# smartGarden_Driver_Rev01.net
KiCad netlist of a schematic drawn in Altium Designer
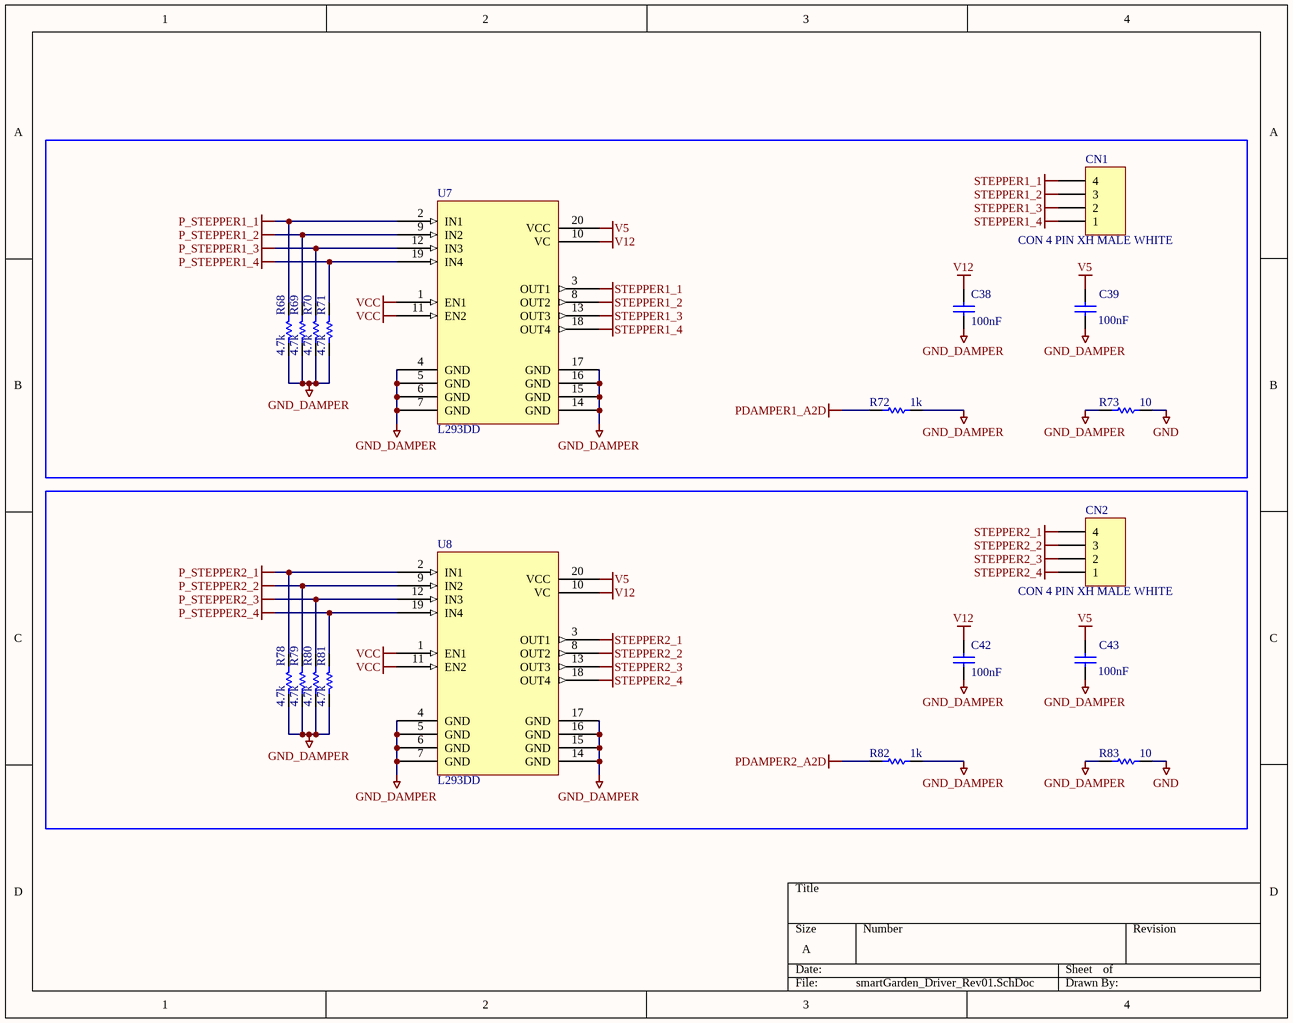
[diagram p0: smartGarden_Driver_Rev01.SchDoc]

(export (version "E")
  (design (tool "Eeschema 10.0.6"))
  (components
    (comp (ref "C38")
      (value "100nF")
      (footprint "0805_SMD")
      (description "Capacitor (Semiconductor SIM Model)")
      (fields (field (name "PUBLISHER") "Altium Limited"))
      (libsource (lib "Miscellaneous Devices") (part "Cap Semi"))
    )
    (comp (ref "C39")
      (value "100nF")
      (footprint "0805_SMD")
      (description "Capacitor (Semiconductor SIM Model)")
      (fields (field (name "PUBLISHER") "Altium Limited"))
      (libsource (lib "Miscellaneous Devices") (part "Cap Semi"))
    )
    (comp (ref "C42")
      (value "100nF")
      (footprint "0805_SMD")
      (description "Capacitor (Semiconductor SIM Model)")
      (fields (field (name "PUBLISHER") "Altium Limited"))
      (libsource (lib "Miscellaneous Devices") (part "Cap Semi"))
    )
    (comp (ref "C43")
      (value "100nF")
      (footprint "0805_SMD")
      (description "Capacitor (Semiconductor SIM Model)")
      (fields (field (name "PUBLISHER") "Altium Limited"))
      (libsource (lib "Miscellaneous Devices") (part "Cap Semi"))
    )
    (comp (ref "CN1")
      (value "CON 4 PIN XH MALE WHITE")
      (footprint "CON4_XH")
      (description "Header, 4-Pin")
      (fields (field (name "PUBLISHER") "Altium Limited"))
      (libsource (lib "Miscellaneous Connectors") (part "Header 4"))
    )
    (comp (ref "CN2")
      (value "CON 4 PIN XH MALE WHITE")
      (footprint "CON4_XH")
      (description "Header, 4-Pin")
      (fields (field (name "PUBLISHER") "Altium Limited"))
      (libsource (lib "Miscellaneous Connectors") (part "Header 4"))
    )
    (comp (ref "R68")
      (value "4.7k")
      (footprint "1206_smd")
      (description "Resistor")
      (fields (field (name "PUBLISHER") "Altium Limited"))
      (libsource (lib "Miscellaneous Devices") (part "Res1"))
    )
    (comp (ref "R69")
      (value "4.7k")
      (footprint "0805_smd")
      (description "Resistor")
      (fields (field (name "PUBLISHER") "Altium Limited"))
      (libsource (lib "Miscellaneous Devices") (part "Res1"))
    )
    (comp (ref "R70")
      (value "4.7k")
      (footprint "0805_smd")
      (description "Resistor")
      (fields (field (name "PUBLISHER") "Altium Limited"))
      (libsource (lib "Miscellaneous Devices") (part "Res1"))
    )
    (comp (ref "R71")
      (value "4.7k")
      (footprint "1206_smd")
      (description "Resistor")
      (fields (field (name "PUBLISHER") "Altium Limited"))
      (libsource (lib "Miscellaneous Devices") (part "Res1"))
    )
    (comp (ref "R72")
      (value "1k")
      (footprint "1206_smd")
      (description "Resistor")
      (fields (field (name "PUBLISHER") "Altium Limited"))
      (libsource (lib "Miscellaneous Devices") (part "Res1"))
    )
    (comp (ref "R73")
      (value "10")
      (footprint "1206_smd")
      (description "Resistor")
      (fields (field (name "PUBLISHER") "Altium Limited"))
      (libsource (lib "Miscellaneous Devices") (part "Res1"))
    )
    (comp (ref "R78")
      (value "4.7k")
      (footprint "1206_smd")
      (description "Resistor")
      (fields (field (name "PUBLISHER") "Altium Limited"))
      (libsource (lib "Miscellaneous Devices") (part "Res1"))
    )
    (comp (ref "R79")
      (value "4.7k")
      (footprint "0805_smd")
      (description "Resistor")
      (fields (field (name "PUBLISHER") "Altium Limited"))
      (libsource (lib "Miscellaneous Devices") (part "Res1"))
    )
    (comp (ref "R80")
      (value "4.7k")
      (footprint "0805_smd")
      (description "Resistor")
      (fields (field (name "PUBLISHER") "Altium Limited"))
      (libsource (lib "Miscellaneous Devices") (part "Res1"))
    )
    (comp (ref "R81")
      (value "4.7k")
      (footprint "1206_smd")
      (description "Resistor")
      (fields (field (name "PUBLISHER") "Altium Limited"))
      (libsource (lib "Miscellaneous Devices") (part "Res1"))
    )
    (comp (ref "R82")
      (value "1k")
      (footprint "1206_smd")
      (description "Resistor")
      (fields (field (name "PUBLISHER") "Altium Limited"))
      (libsource (lib "Miscellaneous Devices") (part "Res1"))
    )
    (comp (ref "R83")
      (value "10")
      (footprint "1206_smd")
      (description "Resistor")
      (fields (field (name "PUBLISHER") "Altium Limited"))
      (libsource (lib "Miscellaneous Devices") (part "Res1"))
    )
    (comp (ref "U7") (value "L293DD") (footprint "SOP20") (libsource (lib "SchLib426") (part "L293DD")))
    (comp (ref "U8") (value "L293DD") (footprint "SOP20") (libsource (lib "SchLib426") (part "L293DD")))
  )
  (nets
    (net (code "1") (name "GND") (class "Default")
      (node (ref "R73") (pin "1") (pinfunction "1_1") (pintype "passive"))
      (node (ref "R83") (pin "1") (pinfunction "1_1") (pintype "passive"))
    )
    (net (code "2") (name "GND_DAMPER") (class "Default")
      (node (ref "C38") (pin "1") (pinfunction "1_1") (pintype "passive"))
      (node (ref "C39") (pin "1") (pinfunction "1_1") (pintype "passive"))
      (node (ref "C42") (pin "1") (pinfunction "1_1") (pintype "passive"))
      (node (ref "C43") (pin "1") (pinfunction "1_1") (pintype "passive"))
      (node (ref "R68") (pin "1") (pinfunction "1_1") (pintype "passive"))
      (node (ref "R69") (pin "1") (pinfunction "1_1") (pintype "passive"))
      (node (ref "R70") (pin "1") (pinfunction "1_1") (pintype "passive"))
      (node (ref "R71") (pin "1") (pinfunction "1_1") (pintype "passive"))
      (node (ref "R72") (pin "1") (pinfunction "1_1") (pintype "passive"))
      (node (ref "R73") (pin "2") (pinfunction "2_2") (pintype "passive"))
      (node (ref "R78") (pin "1") (pinfunction "1_1") (pintype "passive"))
      (node (ref "R79") (pin "1") (pinfunction "1_1") (pintype "passive"))
      (node (ref "R80") (pin "1") (pinfunction "1_1") (pintype "passive"))
      (node (ref "R81") (pin "1") (pinfunction "1_1") (pintype "passive"))
      (node (ref "R82") (pin "1") (pinfunction "1_1") (pintype "passive"))
      (node (ref "R83") (pin "2") (pinfunction "2_2") (pintype "passive"))
      (node (ref "U7") (pin "14") (pinfunction "GND_14") (pintype "power_in"))
      (node (ref "U7") (pin "15") (pinfunction "GND_15") (pintype "power_in"))
      (node (ref "U7") (pin "16") (pinfunction "GND_16") (pintype "power_in"))
      (node (ref "U7") (pin "17") (pinfunction "GND_17") (pintype "power_in"))
      (node (ref "U7") (pin "4") (pinfunction "GND_4") (pintype "power_in"))
      (node (ref "U7") (pin "5") (pinfunction "GND_5") (pintype "power_in"))
      (node (ref "U7") (pin "6") (pinfunction "GND_6") (pintype "power_in"))
      (node (ref "U7") (pin "7") (pinfunction "GND_7") (pintype "power_in"))
      (node (ref "U8") (pin "14") (pinfunction "GND_14") (pintype "power_in"))
      (node (ref "U8") (pin "15") (pinfunction "GND_15") (pintype "power_in"))
      (node (ref "U8") (pin "16") (pinfunction "GND_16") (pintype "power_in"))
      (node (ref "U8") (pin "17") (pinfunction "GND_17") (pintype "power_in"))
      (node (ref "U8") (pin "4") (pinfunction "GND_4") (pintype "power_in"))
      (node (ref "U8") (pin "5") (pinfunction "GND_5") (pintype "power_in"))
      (node (ref "U8") (pin "6") (pinfunction "GND_6") (pintype "power_in"))
      (node (ref "U8") (pin "7") (pinfunction "GND_7") (pintype "power_in"))
    )
    (net (code "3") (name "PDAMPER1_A2D") (class "Default")
      (node (ref "R72") (pin "2") (pinfunction "2_2") (pintype "passive"))
    )
    (net (code "4") (name "PDAMPER2_A2D") (class "Default")
      (node (ref "R82") (pin "2") (pinfunction "2_2") (pintype "passive"))
    )
    (net (code "5") (name "P_STEPPER1_1") (class "Default")
      (node (ref "R68") (pin "2") (pinfunction "2_2") (pintype "passive"))
      (node (ref "U7") (pin "2") (pinfunction "IN1_2") (pintype "input"))
    )
    (net (code "6") (name "P_STEPPER1_2") (class "Default")
      (node (ref "R69") (pin "2") (pinfunction "2_2") (pintype "passive"))
      (node (ref "U7") (pin "9") (pinfunction "IN2_9") (pintype "input"))
    )
    (net (code "7") (name "P_STEPPER1_3") (class "Default")
      (node (ref "R70") (pin "2") (pinfunction "2_2") (pintype "passive"))
      (node (ref "U7") (pin "12") (pinfunction "IN3_12") (pintype "input"))
    )
    (net (code "8") (name "P_STEPPER1_4") (class "Default")
      (node (ref "R71") (pin "2") (pinfunction "2_2") (pintype "passive"))
      (node (ref "U7") (pin "19") (pinfunction "IN4_19") (pintype "input"))
    )
    (net (code "9") (name "P_STEPPER2_1") (class "Default")
      (node (ref "R78") (pin "2") (pinfunction "2_2") (pintype "passive"))
      (node (ref "U8") (pin "2") (pinfunction "IN1_2") (pintype "input"))
    )
    (net (code "10") (name "P_STEPPER2_2") (class "Default")
      (node (ref "R79") (pin "2") (pinfunction "2_2") (pintype "passive"))
      (node (ref "U8") (pin "9") (pinfunction "IN2_9") (pintype "input"))
    )
    (net (code "11") (name "P_STEPPER2_3") (class "Default")
      (node (ref "R80") (pin "2") (pinfunction "2_2") (pintype "passive"))
      (node (ref "U8") (pin "12") (pinfunction "IN3_12") (pintype "input"))
    )
    (net (code "12") (name "P_STEPPER2_4") (class "Default")
      (node (ref "R81") (pin "2") (pinfunction "2_2") (pintype "passive"))
      (node (ref "U8") (pin "19") (pinfunction "IN4_19") (pintype "input"))
    )
    (net (code "13") (name "STEPPER1_1") (class "Default")
      (node (ref "CN1") (pin "4") (pinfunction "4_4") (pintype "passive"))
      (node (ref "U7") (pin "3") (pinfunction "OUT1_3") (pintype "output"))
    )
    (net (code "14") (name "STEPPER1_2") (class "Default")
      (node (ref "CN1") (pin "3") (pinfunction "3_3") (pintype "passive"))
      (node (ref "U7") (pin "8") (pinfunction "OUT2_8") (pintype "output"))
    )
    (net (code "15") (name "STEPPER1_3") (class "Default")
      (node (ref "CN1") (pin "2") (pinfunction "2_2") (pintype "passive"))
      (node (ref "U7") (pin "13") (pinfunction "OUT3_13") (pintype "output"))
    )
    (net (code "16") (name "STEPPER1_4") (class "Default")
      (node (ref "CN1") (pin "1") (pinfunction "1_1") (pintype "passive"))
      (node (ref "U7") (pin "18") (pinfunction "OUT4_18") (pintype "output"))
    )
    (net (code "17") (name "STEPPER2_1") (class "Default")
      (node (ref "CN2") (pin "4") (pinfunction "4_4") (pintype "passive"))
      (node (ref "U8") (pin "3") (pinfunction "OUT1_3") (pintype "output"))
    )
    (net (code "18") (name "STEPPER2_2") (class "Default")
      (node (ref "CN2") (pin "3") (pinfunction "3_3") (pintype "passive"))
      (node (ref "U8") (pin "8") (pinfunction "OUT2_8") (pintype "output"))
    )
    (net (code "19") (name "STEPPER2_3") (class "Default")
      (node (ref "CN2") (pin "2") (pinfunction "2_2") (pintype "passive"))
      (node (ref "U8") (pin "13") (pinfunction "OUT3_13") (pintype "output"))
    )
    (net (code "20") (name "STEPPER2_4") (class "Default")
      (node (ref "CN2") (pin "1") (pinfunction "1_1") (pintype "passive"))
      (node (ref "U8") (pin "18") (pinfunction "OUT4_18") (pintype "output"))
    )
    (net (code "21") (name "V5") (class "Default")
      (node (ref "C39") (pin "2") (pinfunction "2_2") (pintype "passive"))
      (node (ref "C43") (pin "2") (pinfunction "2_2") (pintype "passive"))
      (node (ref "U7") (pin "20") (pinfunction "VCC_20") (pintype "power_in"))
      (node (ref "U8") (pin "20") (pinfunction "VCC_20") (pintype "power_in"))
    )
    (net (code "22") (name "V12") (class "Default")
      (node (ref "C38") (pin "2") (pinfunction "2_2") (pintype "passive"))
      (node (ref "C42") (pin "2") (pinfunction "2_2") (pintype "passive"))
      (node (ref "U7") (pin "10") (pinfunction "VC_10") (pintype "power_in"))
      (node (ref "U8") (pin "10") (pinfunction "VC_10") (pintype "power_in"))
    )
    (net (code "23") (name "VCC") (class "Default")
      (node (ref "U7") (pin "1") (pinfunction "EN1_1") (pintype "input"))
      (node (ref "U7") (pin "11") (pinfunction "EN2_11") (pintype "input"))
      (node (ref "U8") (pin "1") (pinfunction "EN1_1") (pintype "input"))
      (node (ref "U8") (pin "11") (pinfunction "EN2_11") (pintype "input"))
    )
  )
)
